# AstroEQ_SMD_V4_7_EQ5.net
KiCad netlist of a schematic drawn in EAGLE
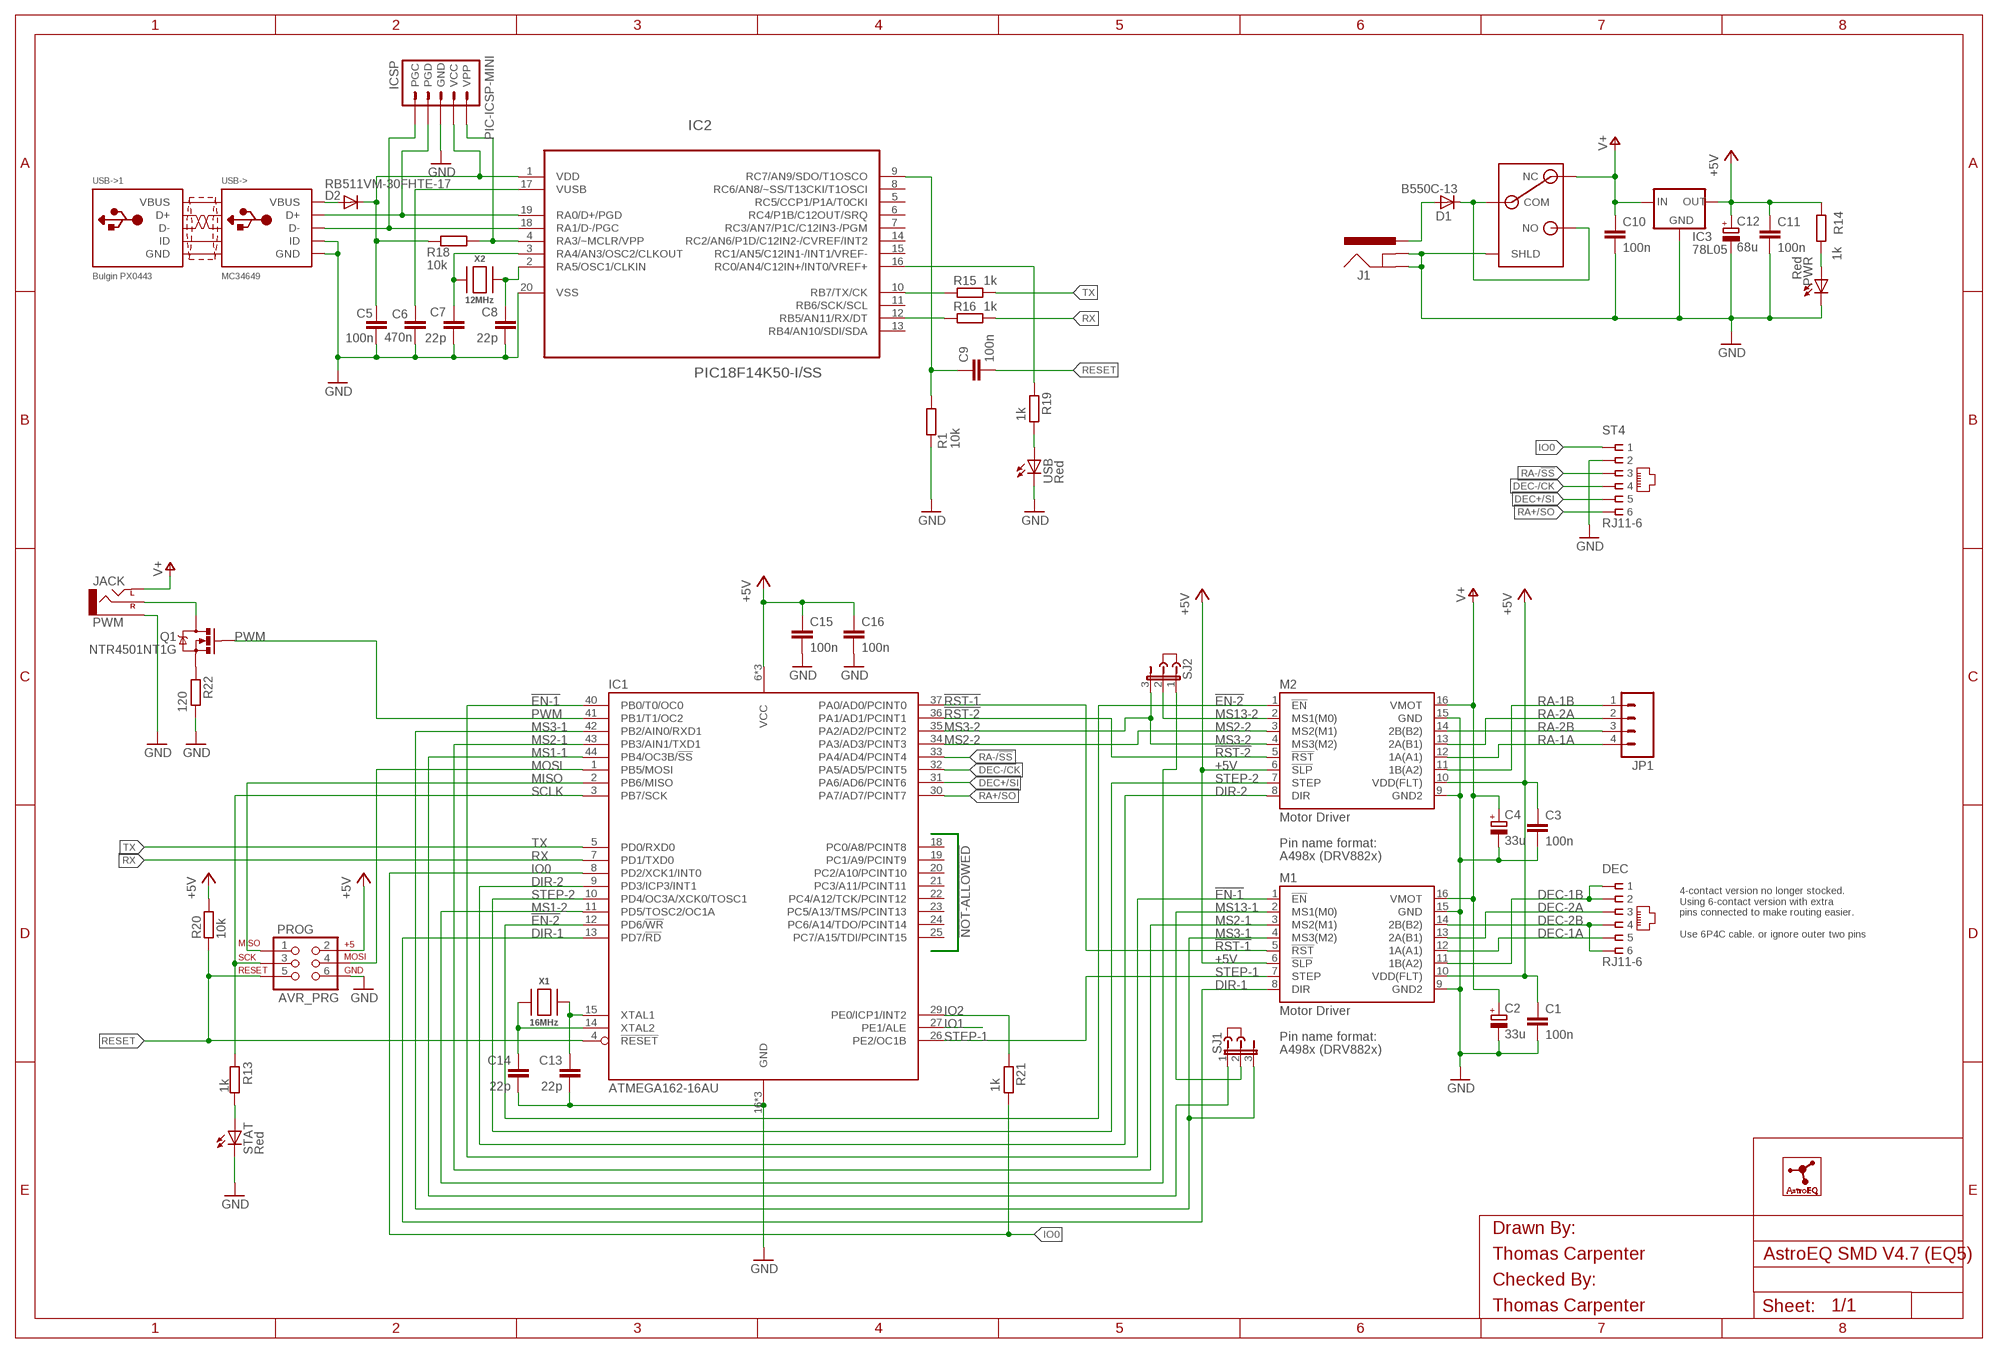
[diagram p0: schematic, sheet 1]

(export (version "E")
  (design (tool "Eeschema 10.0.6"))
  (components
    (comp (ref "C1")
      (value "100n")
      (footprint "eagle-import:C0603")
      (fields (field (name "MF") "MULTICOMP") (field (name "MPN") "MC0603F104Z250CT"))
      (libsource (lib "eagle-import") (part "C-EUC0603"))
    )
    (comp (ref "C2")
      (value "33u")
      (footprint "eagle-import:SMC_C")
      (fields (field (name "MF") "KEMET") (field (name "MPN") "T491C336K025AT"))
      (libsource (lib "eagle-import") (part "CPOL-EUSMCC"))
    )
    (comp (ref "C3")
      (value "100n")
      (footprint "eagle-import:C0603")
      (fields (field (name "MF") "MULTICOMP") (field (name "MPN") "MC0603F104Z250CT"))
      (libsource (lib "eagle-import") (part "C-EUC0603"))
    )
    (comp (ref "C4")
      (value "33u")
      (footprint "eagle-import:SMC_C")
      (fields (field (name "MF") "KEMET") (field (name "MPN") "T491C336K025AT"))
      (libsource (lib "eagle-import") (part "CPOL-EUSMCC"))
    )
    (comp (ref "C5")
      (value "100n")
      (footprint "eagle-import:C0603")
      (fields (field (name "MF") "MULTICOMP") (field (name "MPN") "MC0603F104Z250CT"))
      (libsource (lib "eagle-import") (part "C-EUC0603"))
    )
    (comp (ref "C6")
      (value "470n")
      (footprint "eagle-import:C0603")
      (fields (field (name "MF") "MULTICOMP") (field (name "MPN") "MC0603F474Z160CT"))
      (libsource (lib "eagle-import") (part "C-EUC0603"))
    )
    (comp (ref "C7")
      (value "22p")
      (footprint "eagle-import:C0603")
      (fields (field (name "MF") "MULTICOMP") (field (name "MPN") "MC0603N220J500CT"))
      (libsource (lib "eagle-import") (part "C-EUC0603"))
    )
    (comp (ref "C8")
      (value "22p")
      (footprint "eagle-import:C0603")
      (fields (field (name "MF") "MULTICOMP") (field (name "MPN") "MC0603N220J500CT"))
      (libsource (lib "eagle-import") (part "C-EUC0603"))
    )
    (comp (ref "C9")
      (value "100n")
      (footprint "eagle-import:C0603")
      (fields (field (name "MF") "MULTICOMP") (field (name "MPN") "MC0603F104Z250CT"))
      (libsource (lib "eagle-import") (part "C-EUC0603"))
    )
    (comp (ref "C10")
      (value "100n")
      (footprint "eagle-import:C0603")
      (fields (field (name "MF") "MULTICOMP") (field (name "MPN") "MC0603F104Z250CT"))
      (libsource (lib "eagle-import") (part "C-EUC0603"))
    )
    (comp (ref "C11")
      (value "100n")
      (footprint "eagle-import:C0603")
      (fields (field (name "MF") "MULTICOMP") (field (name "MPN") "MC0603F104Z250CT"))
      (libsource (lib "eagle-import") (part "C-EUC0603"))
    )
    (comp (ref "C12")
      (value "68u")
      (footprint "eagle-import:SMC_C")
      (fields (field (name "MF") "AVX") (field (name "MPN") "TPSC686K016R0125"))
      (libsource (lib "eagle-import") (part "CPOL-EUSMCC"))
    )
    (comp (ref "C13")
      (value "22p")
      (footprint "eagle-import:C0603")
      (fields (field (name "MF") "MULTICOMP") (field (name "MPN") "MC0603N220J500CT"))
      (libsource (lib "eagle-import") (part "C-EUC0603"))
    )
    (comp (ref "C14")
      (value "22p")
      (footprint "eagle-import:C0603")
      (fields (field (name "MF") "MULTICOMP") (field (name "MPN") "MC0603N220J500CT"))
      (libsource (lib "eagle-import") (part "C-EUC0603"))
    )
    (comp (ref "C15")
      (value "100n")
      (footprint "eagle-import:C0603")
      (fields (field (name "MF") "MULTICOMP") (field (name "MPN") "MC0603F104Z250CT"))
      (libsource (lib "eagle-import") (part "C-EUC0603"))
    )
    (comp (ref "C16")
      (value "100n")
      (footprint "eagle-import:C0603")
      (fields (field (name "MF") "MULTICOMP") (field (name "MPN") "MC0603F104Z250CT"))
      (libsource (lib "eagle-import") (part "C-EUC0603"))
    )
    (comp (ref "D1")
      (value "B550C-13")
      (footprint "eagle-import:SMC")
      (fields (field (name "MF") "DIODES INC.") (field (name "MPN") "B550C-13-F"))
      (libsource (lib "eagle-import") (part "DIODE-SMC"))
    )
    (comp (ref "D2")
      (value "RB511VM-30FHTE-17")
      (footprint "eagle-import:SOD-323")
      (fields (field (name "MF") "ROHM"))
      (libsource (lib "eagle-import") (part "DIODESOD"))
    )
    (comp (ref "DEC")
      (value "RJ11-6")
      (footprint "eagle-import:RJ11-NO_SHIELD")
      (fields
        (field (name "MF") "TYCO ELECTRONICS")
        (field (name "MPN") "RJ11-2L-B")
        (field (name "MF_1") "MOLEX")
        (field (name "MPN_1") "95503-2661")
        (field (name "OC_FARNELL") "1620210")
      )
      (libsource (lib "eagle-import") (part "RJ11-2L-B"))
    )
    (comp (ref "IC1")
      (value "ATMEGA162-16AU")
      (footprint "eagle-import:TQFP44")
      (fields (field (name "MF") "ATMEL"))
      (libsource (lib "eagle-import") (part "ATMEGA162-16AU"))
    )
    (comp (ref "IC2")
      (value "PIC18F14K50-I/SS")
      (footprint "eagle-import:SS20")
      (fields (field (name "MF") "MICROCHIP"))
      (libsource (lib "eagle-import") (part "PIC18F14K50/SS-I"))
    )
    (comp (ref "IC3")
      (value "78L05")
      (footprint "eagle-import:SOT23")
      (fields (field (name "MF") "TAIWAN SEMICONDUCTOR") (field (name "MPN") "TS78L05CX RFG"))
      (libsource (lib "eagle-import") (part "78LXXSOT-23"))
    )
    (comp (ref "ICSP")
      (value "PIC-ICSP-MINI")
      (footprint "eagle-import:PIC-ICSP-MINI")
      (libsource (lib "eagle-import") (part "PIC-ICSP-MINI"))
    )
    (comp (ref "J1")
      (value "POWER_JACKPANEL")
      (footprint "eagle-import:POWER_JACK_PANEL")
      (fields (field (name "MF") "SWITCHCRAFT") (field (name "MPN") "PCL712AS"))
      (libsource (lib "eagle-import") (part "POWER_JACKPANEL"))
    )
    (comp (ref "J2")
      (value "JUMPER")
      (footprint "eagle-import:JUMP")
      (fields (field (name "MF") "3M") (field (name "MPN") "969102-0000-DA"))
      (libsource (lib "eagle-import") (part "JUMPER"))
    )
    (comp (ref "J3")
      (value "JUMPER")
      (footprint "eagle-import:JUMP")
      (fields (field (name "MF") "3M") (field (name "MPN") "969102-0000-DA"))
      (libsource (lib "eagle-import") (part "JUMPER"))
    )
    (comp (ref "JP1")
      (value "M04POLAR")
      (footprint "eagle-import:MOLEX-1X4")
      (fields (field (name "MF") "MULTICOMP") (field (name "MPN") "MC34645"))
      (libsource (lib "eagle-import") (part "M04POLAR"))
    )
    (comp (ref "LOGO1")
      (value "ASTROEQ5MM")
      (footprint "eagle-import:ASTROEQ-SMALL")
      (libsource (lib "eagle-import") (part "ASTROEQ5MM"))
    )
    (comp (ref "M1")
      (value "Motor Driver")
      (footprint "eagle-import:DIP16-W")
      (fields (field (name "MF") "SAMTEC") (field (name "MPN") "CES-116-01-T-S"))
      (libsource (lib "eagle-import") (part "A4983CARRIER"))
    )
    (comp (ref "M2")
      (value "Motor Driver")
      (footprint "eagle-import:DIP16-W")
      (fields (field (name "MF") "SAMTEC") (field (name "MPN") "CES-116-01-T-S"))
      (libsource (lib "eagle-import") (part "A4983CARRIER"))
    )
    (comp (ref "PROG")
      (value "AVR_PRG")
      (footprint "eagle-import:2X3")
      (fields (field (name "MF") "AMP - TE CONNECTIVITY") (field (name "MPN") "826632-3"))
      (libsource (lib "eagle-import") (part "AVR_SPI_PRG_6PTH"))
    )
    (comp (ref "PWM")
      (value "JACK")
      (footprint "eagle-import:AUDIO-JACK-3.5MM-VERT")
      (fields (field (name "MANUFACTURER") "LUMBERG") (field (name "MPN") "1502 01"))
      (libsource (lib "eagle-import") (part "AUDIO-JACKVERT"))
    )
    (comp (ref "PWR")
      (value "Red")
      (footprint "eagle-import:LED3MM")
      (fields (field (name "MF") "KINGBRIGHT") (field (name "MPN") "L-424HDT"))
      (libsource (lib "eagle-import") (part "LED3MM"))
    )
    (comp (ref "PWR-SW")
      (value "SWITCH")
      (footprint "eagle-import:SPST")
      (fields (field (name "MF") "TE CONNECTIVITY") (field (name "MPN") "AE101J1V3B004"))
      (libsource (lib "eagle-import") (part "SWITCH"))
    )
    (comp (ref "Q1")
      (value "NTR4501NT1G")
      (footprint "eagle-import:SOT23-3")
      (fields (field (name "MF") "ON SEMICONDUCTOR"))
      (libsource (lib "eagle-import") (part "MOSFET-NCHANNELSMD"))
    )
    (comp (ref "R1")
      (value "10k")
      (footprint "eagle-import:R0603")
      (fields (field (name "MF") "MULTICOMP") (field (name "MPN") "MCWR06X1002FTL"))
      (libsource (lib "eagle-import") (part "R-EU_R0603"))
    )
    (comp (ref "R13")
      (value "1k")
      (footprint "eagle-import:R0603")
      (fields (field (name "MF") "MULTICOMP") (field (name "MPN") "MCWR06X1001FTL"))
      (libsource (lib "eagle-import") (part "R-EU_R0603"))
    )
    (comp (ref "R14")
      (value "1k")
      (footprint "eagle-import:R0603")
      (fields (field (name "MF") "MULTICOMP") (field (name "MPN") "MCWR06X1001FTL"))
      (libsource (lib "eagle-import") (part "R-EU_R0603"))
    )
    (comp (ref "R15")
      (value "1k")
      (footprint "eagle-import:R0603")
      (fields (field (name "MF") "MULTICOMP") (field (name "MPN") "MCWR06X1001FTL"))
      (libsource (lib "eagle-import") (part "R-EU_R0603"))
    )
    (comp (ref "R16")
      (value "1k")
      (footprint "eagle-import:R0603")
      (fields (field (name "MF") "MULTICOMP") (field (name "MPN") "MCWR06X1001FTL"))
      (libsource (lib "eagle-import") (part "R-EU_R0603"))
    )
    (comp (ref "R18")
      (value "10k")
      (footprint "eagle-import:R0603")
      (fields (field (name "MF") "MULTICOMP") (field (name "MPN") "MCWR06X1002FTL"))
      (libsource (lib "eagle-import") (part "R-EU_R0603"))
    )
    (comp (ref "R19")
      (value "1k")
      (footprint "eagle-import:R0603")
      (fields (field (name "MF") "MULTICOMP") (field (name "MPN") "MCWR06X1001FTL"))
      (libsource (lib "eagle-import") (part "R-EU_R0603"))
    )
    (comp (ref "R20")
      (value "10k")
      (footprint "eagle-import:R0603")
      (fields (field (name "MF") "MULTICOMP") (field (name "MPN") "MCWR06X1002FTL"))
      (libsource (lib "eagle-import") (part "R-EU_R0603"))
    )
    (comp (ref "R21")
      (value "1k")
      (footprint "eagle-import:R0603")
      (fields (field (name "MF") "MULTICOMP") (field (name "MPN") "MCWR06X1001FTL"))
      (libsource (lib "eagle-import") (part "R-EU_R0603"))
    )
    (comp (ref "R22")
      (value "120")
      (footprint "eagle-import:R0805")
      (fields (field (name "MF") "MULTICOMP") (field (name "MPN") "MCWR08X1200FTL"))
      (libsource (lib "eagle-import") (part "R-EU_R0805"))
    )
    (comp (ref "SJ1")
      (value "JP2E")
      (footprint "eagle-import:JP2")
      (fields (field (name "MF") "MULTICOMP") (field (name "MPN") "2211S-03G"))
      (libsource (lib "eagle-import") (part "JP2E"))
    )
    (comp (ref "SJ2")
      (value "JP2E")
      (footprint "eagle-import:JP2")
      (fields (field (name "MF") "MULTICOMP") (field (name "MPN") "2211S-03G"))
      (libsource (lib "eagle-import") (part "JP2E"))
    )
    (comp (ref "ST4")
      (value "RJ11-6")
      (footprint "eagle-import:RJ11-NO_SHIELD")
      (fields
        (field (name "MF") "TYCO ELECTRONICS")
        (field (name "MPN") "RJ11-2L-B")
        (field (name "MF_1") "MOLEX")
        (field (name "MPN_1") "95503-2661")
        (field (name "OC_FARNELL") "1620210")
      )
      (libsource (lib "eagle-import") (part "RJ11-2L-B"))
    )
    (comp (ref "STAT")
      (value "Red")
      (footprint "eagle-import:LED3MM")
      (fields (field (name "MF") "KINGBRIGHT") (field (name "MPN") "L-424HDT"))
      (libsource (lib "eagle-import") (part "LED3MM"))
    )
    (comp (ref "USB")
      (value "Red")
      (footprint "eagle-import:LED3MM")
      (fields (field (name "MF") "KINGBRIGHT") (field (name "MPN") "L-424HDT"))
      (libsource (lib "eagle-import") (part "LED3MM"))
    )
    (comp (ref "USB->")
      (value "MC34649")
      (footprint "eagle-import:22-23-2051")
      (fields (field (name "MF") "MULTICOMP"))
      (libsource (lib "eagle-import") (part "USBBULGINWIRE"))
    )
    (comp (ref "X1")
      (value "16MHz")
      (footprint "eagle-import:NX5032")
      (fields (field (name "MF") "TXC") (field (name "MPN") "7A-16.000MAAJ-T"))
      (libsource (lib "eagle-import") (part "XTALNX5032"))
    )
    (comp (ref "X2")
      (value "12MHz")
      (footprint "eagle-import:NX5032")
      (fields (field (name "MF") "TXC") (field (name "MPN") "7A-12.000MAAJ-T"))
      (libsource (lib "eagle-import") (part "XTALNX5032"))
    )
  )
  (nets
    (net (code "1") (name "+5V") (class "Default")
      (node (ref "C1") (pin "1") (pinfunction "1_1") (pintype "passive"))
      (node (ref "C11") (pin "1") (pinfunction "1_1") (pintype "passive"))
      (node (ref "C12") (pin "+") (pinfunction "+_+") (pintype "passive"))
      (node (ref "C15") (pin "1") (pinfunction "1_1") (pintype "passive"))
      (node (ref "C16") (pin "1") (pinfunction "1_1") (pintype "passive"))
      (node (ref "C3") (pin "1") (pinfunction "1_1") (pintype "passive"))
      (node (ref "IC1") (pin "17") (pinfunction "VCC_17") (pintype "power_in"))
      (node (ref "IC1") (pin "38") (pinfunction "VCC_38") (pintype "power_in"))
      (node (ref "IC1") (pin "6") (pinfunction "VCC_6") (pintype "power_in"))
      (node (ref "IC3") (pin "1") (pinfunction "OUT_1") (pintype "passive"))
      (node (ref "M1") (pin "10") (pinfunction "VDD(FLT)_10") (pintype "power_in"))
      (node (ref "M1") (pin "6") (pinfunction "~{SLP}_6") (pintype "input"))
      (node (ref "M2") (pin "10") (pinfunction "VDD(FLT)_10") (pintype "power_in"))
      (node (ref "M2") (pin "6") (pinfunction "~{SLP}_6") (pintype "input"))
      (node (ref "PROG") (pin "2") (pinfunction "2_2") (pintype "passive"))
      (node (ref "R14") (pin "1") (pinfunction "1_1") (pintype "passive"))
      (node (ref "R20") (pin "2") (pinfunction "2_2") (pintype "passive"))
    )
    (net (code "2") (name "/DEC-1A") (class "Default")
      (node (ref "DEC") (pin "5") (pinfunction "5_5") (pintype "passive"))
      (node (ref "M1") (pin "12") (pinfunction "1A(A1)_12") (pintype "output"))
    )
    (net (code "3") (name "/DEC-1B") (class "Default")
      (node (ref "DEC") (pin "1") (pinfunction "1_1") (pintype "passive"))
      (node (ref "DEC") (pin "2") (pinfunction "2_2") (pintype "passive"))
      (node (ref "M1") (pin "11") (pinfunction "1B(A2)_11") (pintype "output"))
    )
    (net (code "4") (name "/DEC-2A") (class "Default")
      (node (ref "DEC") (pin "3") (pinfunction "3_3") (pintype "passive"))
      (node (ref "M1") (pin "13") (pinfunction "2A(B1)_13") (pintype "output"))
    )
    (net (code "5") (name "/DEC-2B") (class "Default")
      (node (ref "DEC") (pin "4") (pinfunction "4_4") (pintype "passive"))
      (node (ref "DEC") (pin "6") (pinfunction "6_6") (pintype "passive"))
      (node (ref "M1") (pin "14") (pinfunction "2B(B2)_14") (pintype "output"))
    )
    (net (code "6") (name "/DIR-1") (class "Default")
      (node (ref "IC1") (pin "13") (pinfunction "PD7/~{RD}_13") (pintype "bidirectional"))
      (node (ref "M1") (pin "8") (pinfunction "DIR_8") (pintype "input"))
    )
    (net (code "7") (name "/DIR-2") (class "Default")
      (node (ref "IC1") (pin "9") (pinfunction "PD3/ICP3/INT1_9") (pintype "bidirectional"))
      (node (ref "M2") (pin "8") (pinfunction "DIR_8") (pintype "input"))
    )
    (net (code "8") (name "/IO1") (class "Default")
      (node (ref "IC1") (pin "27") (pinfunction "PE1/ALE_27") (pintype "bidirectional"))
    )
    (net (code "9") (name "/IO2") (class "Default")
      (node (ref "IC1") (pin "29") (pinfunction "PE0/ICP1/INT2_29") (pintype "bidirectional"))
      (node (ref "R21") (pin "2") (pinfunction "2_2") (pintype "passive"))
    )
    (net (code "10") (name "/MISO") (class "Default")
      (node (ref "IC1") (pin "2") (pinfunction "PB6/MISO_2") (pintype "bidirectional"))
      (node (ref "PROG") (pin "1") (pinfunction "1_1") (pintype "passive"))
    )
    (net (code "11") (name "/MOSI") (class "Default")
      (node (ref "IC1") (pin "1") (pinfunction "PB5/MOSI_1") (pintype "bidirectional"))
      (node (ref "PROG") (pin "4") (pinfunction "4_4") (pintype "passive"))
    )
    (net (code "12") (name "/MS1-1") (class "Default")
      (node (ref "IC1") (pin "44") (pinfunction "PB4/OC3B/~{SS}_44") (pintype "bidirectional"))
      (node (ref "SJ1") (pin "1") (pinfunction "1_1") (pintype "passive"))
    )
    (net (code "13") (name "/MS1-2") (class "Default")
      (node (ref "IC1") (pin "11") (pinfunction "PD5/TOSC2/OC1A_11") (pintype "bidirectional"))
      (node (ref "SJ2") (pin "1") (pinfunction "1_1") (pintype "passive"))
    )
    (net (code "14") (name "/MS2-1") (class "Default")
      (node (ref "IC1") (pin "43") (pinfunction "PB3/AIN1/TXD1_43") (pintype "bidirectional"))
      (node (ref "M1") (pin "3") (pinfunction "MS2(M1)_3") (pintype "input"))
    )
    (net (code "15") (name "/MS2-2") (class "Default")
      (node (ref "IC1") (pin "34") (pinfunction "PA3/AD3/PCINT3_34") (pintype "bidirectional"))
      (node (ref "M2") (pin "3") (pinfunction "MS2(M1)_3") (pintype "input"))
    )
    (net (code "16") (name "/MS3-1") (class "Default")
      (node (ref "IC1") (pin "42") (pinfunction "PB2/AIN0/RXD1_42") (pintype "bidirectional"))
      (node (ref "M1") (pin "4") (pinfunction "MS3(M2)_4") (pintype "input"))
      (node (ref "SJ1") (pin "3") (pinfunction "3_3") (pintype "passive"))
    )
    (net (code "17") (name "/MS3-2") (class "Default")
      (node (ref "IC1") (pin "35") (pinfunction "PA2/AD2/PCINT2_35") (pintype "bidirectional"))
      (node (ref "M2") (pin "4") (pinfunction "MS3(M2)_4") (pintype "input"))
      (node (ref "SJ2") (pin "3") (pinfunction "3_3") (pintype "passive"))
    )
    (net (code "18") (name "/MS13-1") (class "Default")
      (node (ref "M1") (pin "2") (pinfunction "MS1(M0)_2") (pintype "input"))
      (node (ref "SJ1") (pin "2") (pinfunction "2_2") (pintype "passive"))
    )
    (net (code "19") (name "/MS13-2") (class "Default")
      (node (ref "M2") (pin "2") (pinfunction "MS1(M0)_2") (pintype "input"))
      (node (ref "SJ2") (pin "2") (pinfunction "2_2") (pintype "passive"))
    )
    (net (code "20") (name "/PWM") (class "Default")
      (node (ref "IC1") (pin "41") (pinfunction "PB1/T1/OC2_41") (pintype "bidirectional"))
      (node (ref "Q1") (pin "1") (pinfunction "G_1") (pintype "passive"))
    )
    (net (code "21") (name "/RA-1A") (class "Default")
      (node (ref "JP1") (pin "4") (pinfunction "4_4") (pintype "passive"))
      (node (ref "M2") (pin "12") (pinfunction "1A(A1)_12") (pintype "output"))
    )
    (net (code "22") (name "/RA-1B") (class "Default")
      (node (ref "JP1") (pin "1") (pinfunction "1_1") (pintype "passive"))
      (node (ref "M2") (pin "11") (pinfunction "1B(A2)_11") (pintype "output"))
    )
    (net (code "23") (name "/RA-2A") (class "Default")
      (node (ref "JP1") (pin "2") (pinfunction "2_2") (pintype "passive"))
      (node (ref "M2") (pin "13") (pinfunction "2A(B1)_13") (pintype "output"))
    )
    (net (code "24") (name "/RA-2B") (class "Default")
      (node (ref "JP1") (pin "3") (pinfunction "3_3") (pintype "passive"))
      (node (ref "M2") (pin "14") (pinfunction "2B(B2)_14") (pintype "output"))
    )
    (net (code "25") (name "/RA-{slash}~{SS}") (class "Default")
      (node (ref "IC1") (pin "33") (pinfunction "PA4/AD4/PCINT4_33") (pintype "bidirectional"))
      (node (ref "ST4") (pin "3") (pinfunction "3_3") (pintype "passive"))
    )
    (net (code "26") (name "/SCLK") (class "Default")
      (node (ref "IC1") (pin "3") (pinfunction "PB7/SCK_3") (pintype "bidirectional"))
      (node (ref "PROG") (pin "3") (pinfunction "3_3") (pintype "passive"))
      (node (ref "R13") (pin "1") (pinfunction "1_1") (pintype "passive"))
    )
    (net (code "27") (name "/STEP-1") (class "Default")
      (node (ref "IC1") (pin "26") (pinfunction "PE2/OC1B_26") (pintype "bidirectional"))
      (node (ref "M1") (pin "7") (pinfunction "STEP_7") (pintype "input"))
    )
    (net (code "28") (name "/STEP-2") (class "Default")
      (node (ref "IC1") (pin "10") (pinfunction "PD4/OC3A/XCK0/TOSC1_10") (pintype "bidirectional"))
      (node (ref "M2") (pin "7") (pinfunction "STEP_7") (pintype "input"))
    )
    (net (code "29") (name "/~{EN-1}") (class "Default")
      (node (ref "IC1") (pin "40") (pinfunction "PB0/T0/OC0_40") (pintype "bidirectional"))
      (node (ref "M1") (pin "1") (pinfunction "~{EN}_1") (pintype "input"))
    )
    (net (code "30") (name "/~{EN-2}") (class "Default")
      (node (ref "IC1") (pin "12") (pinfunction "PD6/~{WR}_12") (pintype "bidirectional"))
      (node (ref "M2") (pin "1") (pinfunction "~{EN}_1") (pintype "input"))
    )
    (net (code "32") (name "/~{RST-1}") (class "Default")
      (node (ref "IC1") (pin "37") (pinfunction "PA0/AD0/PCINT0_37") (pintype "bidirectional"))
      (node (ref "M1") (pin "5") (pinfunction "~{RST}_5") (pintype "input"))
    )
    (net (code "33") (name "/~{RST-2}") (class "Default")
      (node (ref "IC1") (pin "36") (pinfunction "PA1/AD1/PCINT1_36") (pintype "bidirectional"))
      (node (ref "M2") (pin "5") (pinfunction "~{RST}_5") (pintype "input"))
    )
    (net (code "34") (name "DEC+{slash}SI") (class "Default")
      (node (ref "IC1") (pin "31") (pinfunction "PA6/AD6/PCINT6_31") (pintype "bidirectional"))
      (node (ref "ST4") (pin "5") (pinfunction "5_5") (pintype "passive"))
    )
    (net (code "35") (name "DEC-{slash}CK") (class "Default")
      (node (ref "IC1") (pin "32") (pinfunction "PA5/AD5/PCINT5_32") (pintype "bidirectional"))
      (node (ref "ST4") (pin "4") (pinfunction "4_4") (pintype "passive"))
    )
    (net (code "36") (name "GND") (class "Default")
      (node (ref "C1") (pin "2") (pinfunction "2_2") (pintype "passive"))
      (node (ref "C10") (pin "2") (pinfunction "2_2") (pintype "passive"))
      (node (ref "C11") (pin "2") (pinfunction "2_2") (pintype "passive"))
      (node (ref "C12") (pin "-") (pinfunction "-_-") (pintype "passive"))
      (node (ref "C13") (pin "2") (pinfunction "2_2") (pintype "passive"))
      (node (ref "C14") (pin "2") (pinfunction "2_2") (pintype "passive"))
      (node (ref "C15") (pin "2") (pinfunction "2_2") (pintype "passive"))
      (node (ref "C16") (pin "2") (pinfunction "2_2") (pintype "passive"))
      (node (ref "C2") (pin "-") (pinfunction "-_-") (pintype "passive"))
      (node (ref "C3") (pin "2") (pinfunction "2_2") (pintype "passive"))
      (node (ref "C4") (pin "-") (pinfunction "-_-") (pintype "passive"))
      (node (ref "C5") (pin "2") (pinfunction "2_2") (pintype "passive"))
      (node (ref "C6") (pin "1") (pinfunction "1_1") (pintype "passive"))
      (node (ref "C7") (pin "2") (pinfunction "2_2") (pintype "passive"))
      (node (ref "C8") (pin "2") (pinfunction "2_2") (pintype "passive"))
      (node (ref "IC1") (pin "16") (pinfunction "GND_16") (pintype "power_in"))
      (node (ref "IC1") (pin "28") (pinfunction "GND_28") (pintype "power_in"))
      (node (ref "IC1") (pin "39") (pinfunction "GND_39") (pintype "power_in"))
      (node (ref "IC2") (pin "20") (pinfunction "VSS_20") (pintype "power_in"))
      (node (ref "IC3") (pin "3") (pinfunction "GND_3") (pintype "input"))
      (node (ref "ICSP") (pin "3") (pinfunction "GND_3") (pintype "passive"))
      (node (ref "J1") (pin "SHUNT") (pinfunction "GNDBREAK_SHUNT") (pintype "bidirectional"))
      (node (ref "J1") (pin "SLEEVE") (pinfunction "GND_SLEEVE") (pintype "bidirectional"))
      (node (ref "M1") (pin "15") (pinfunction "GND_15") (pintype "power_in"))
      (node (ref "M1") (pin "9") (pinfunction "GND2_9") (pintype "power_in"))
      (node (ref "M2") (pin "15") (pinfunction "GND_15") (pintype "power_in"))
      (node (ref "M2") (pin "9") (pinfunction "GND2_9") (pintype "power_in"))
      (node (ref "PROG") (pin "6") (pinfunction "6_6") (pintype "passive"))
      (node (ref "PWM") (pin "1") (pinfunction "SLEEVE_1") (pintype "bidirectional"))
      (node (ref "PWR") (pin "K") (pinfunction "C_K") (pintype "passive"))
      (node (ref "PWR-SW") (pin "S1") (pinfunction "SHLD_S1") (pintype "bidirectional"))
      (node (ref "PWR-SW") (pin "S2") (pinfunction "SHLD_S2") (pintype "bidirectional"))
      (node (ref "PWR-SW") (pin "S3") (pinfunction "SHLD_S3") (pintype "bidirectional"))
      (node (ref "PWR-SW") (pin "S4") (pinfunction "SHLD_S4") (pintype "bidirectional"))
      (node (ref "R1") (pin "2") (pinfunction "2_2") (pintype "passive"))
      (node (ref "R22") (pin "1") (pinfunction "1_1") (pintype "passive"))
      (node (ref "ST4") (pin "2") (pinfunction "2_2") (pintype "passive"))
      (node (ref "STAT") (pin "K") (pinfunction "C_K") (pintype "passive"))
      (node (ref "USB") (pin "K") (pinfunction "C_K") (pintype "passive"))
      (node (ref "USB->") (pin "4") (pinfunction "GND_4") (pintype "power_in"))
      (node (ref "USB->") (pin "5") (pinfunction "ID_5") (pintype "bidirectional"))
    )
    (net (code "37") (name "IO0") (class "Default")
      (node (ref "IC1") (pin "8") (pinfunction "PD2/XCK1/INT0_8") (pintype "bidirectional"))
      (node (ref "R21") (pin "1") (pinfunction "1_1") (pintype "passive"))
      (node (ref "ST4") (pin "1") (pinfunction "1_1") (pintype "passive"))
    )
    (net (code "38") (name "Net-(D1-PadC)") (class "Default")
      (node (ref "D1") (pin "C") (pinfunction "C_C") (pintype "passive"))
      (node (ref "PWR-SW") (pin "COM") (pinfunction "COM_COM") (pintype "passive"))
      (node (ref "PWR-SW") (pin "NO") (pinfunction "NO_NO") (pintype "passive"))
    )
    (net (code "39") (name "Net-(D2-A)") (class "Default")
      (node (ref "D2") (pin "2") (pinfunction "A_2") (pintype "passive"))
      (node (ref "USB->") (pin "1") (pinfunction "VBUS_1") (pintype "power_in"))
    )
    (net (code "40") (name "Net-(D2-C)") (class "Default")
      (node (ref "C5") (pin "1") (pinfunction "1_1") (pintype "passive"))
      (node (ref "D2") (pin "1") (pinfunction "C_1") (pintype "passive"))
      (node (ref "IC2") (pin "1") (pinfunction "VDD_1") (pintype "power_in"))
      (node (ref "ICSP") (pin "2") (pinfunction "VCC_2") (pintype "passive"))
      (node (ref "R18") (pin "2") (pinfunction "2_2") (pintype "passive"))
    )
    (net (code "41") (name "Net-(IC1-XTAL1)") (class "Default")
      (node (ref "C13") (pin "1") (pinfunction "1_1") (pintype "passive"))
      (node (ref "IC1") (pin "15") (pinfunction "XTAL1_15") (pintype "input"))
      (node (ref "X1") (pin "P$1") (pinfunction "P$1_P$1") (pintype "bidirectional"))
    )
    (net (code "42") (name "Net-(IC1-XTAL2)") (class "Default")
      (node (ref "C14") (pin "1") (pinfunction "1_1") (pintype "passive"))
      (node (ref "IC1") (pin "14") (pinfunction "XTAL2_14") (pintype "input"))
      (node (ref "X1") (pin "P$2") (pinfunction "P$2_P$2") (pintype "bidirectional"))
    )
    (net (code "43") (name "Net-(IC2-RA0{slash}D+{slash}PGD)") (class "Default")
      (node (ref "IC2") (pin "19") (pinfunction "RA0/D+/PGD_19") (pintype "bidirectional"))
      (node (ref "ICSP") (pin "4") (pinfunction "PGD_4") (pintype "passive"))
      (node (ref "USB->") (pin "3") (pinfunction "D+_3") (pintype "bidirectional"))
    )
    (net (code "44") (name "Net-(IC2-RA1{slash}D-{slash}PGC)") (class "Default")
      (node (ref "IC2") (pin "18") (pinfunction "RA1/D-/PGC_18") (pintype "bidirectional"))
      (node (ref "ICSP") (pin "5") (pinfunction "PGC_5") (pintype "passive"))
      (node (ref "USB->") (pin "2") (pinfunction "D-_2") (pintype "bidirectional"))
    )
    (net (code "45") (name "Net-(IC2-RA3{slash}~{MCLR{slash}VPP})") (class "Default")
      (node (ref "IC2") (pin "4") (pinfunction "RA3/~{MCLR/VPP}_4") (pintype "input"))
      (node (ref "ICSP") (pin "1") (pinfunction "VPP_1") (pintype "passive"))
      (node (ref "R18") (pin "1") (pinfunction "1_1") (pintype "passive"))
    )
    (net (code "46") (name "Net-(IC2-RA4{slash}AN3{slash}OSC2{slash}CLKOUT)") (class "Default")
      (node (ref "C7") (pin "1") (pinfunction "1_1") (pintype "passive"))
      (node (ref "IC2") (pin "3") (pinfunction "RA4/AN3/OSC2/CLKOUT_3") (pintype "bidirectional"))
      (node (ref "X2") (pin "P$1") (pinfunction "P$1_P$1") (pintype "bidirectional"))
    )
    (net (code "47") (name "Net-(IC2-RA5{slash}OSC1{slash}CLKIN)") (class "Default")
      (node (ref "C8") (pin "1") (pinfunction "1_1") (pintype "passive"))
      (node (ref "IC2") (pin "2") (pinfunction "RA5/OSC1/CLKIN_2") (pintype "bidirectional"))
      (node (ref "X2") (pin "P$2") (pinfunction "P$2_P$2") (pintype "bidirectional"))
    )
    (net (code "48") (name "Net-(IC2-RB5{slash}AN11{slash}RX{slash}DT)") (class "Default")
      (node (ref "IC2") (pin "12") (pinfunction "RB5/AN11/RX/DT_12") (pintype "bidirectional"))
      (node (ref "R16") (pin "2") (pinfunction "2_2") (pintype "passive"))
    )
    (net (code "49") (name "Net-(IC2-RB7{slash}TX{slash}CK)") (class "Default")
      (node (ref "IC2") (pin "10") (pinfunction "RB7/TX/CK_10") (pintype "bidirectional"))
      (node (ref "R15") (pin "2") (pinfunction "2_2") (pintype "passive"))
    )
    (net (code "50") (name "Net-(IC2-RC0{slash}AN4{slash}C12IN+{slash}INT0{slash}VREF+)") (class "Default")
      (node (ref "IC2") (pin "16") (pinfunction "RC0/AN4/C12IN+/INT0/VREF+_16") (pintype "bidirectional"))
      (node (ref "R19") (pin "2") (pinfunction "2_2") (pintype "passive"))
    )
    (net (code "51") (name "Net-(IC2-RC7{slash}AN9{slash}SDO{slash}T1OSCO)") (class "Default")
      (node (ref "C9") (pin "1") (pinfunction "1_1") (pintype "passive"))
      (node (ref "IC2") (pin "9") (pinfunction "RC7/AN9/SDO/T1OSCO_9") (pintype "bidirectional"))
      (node (ref "R1") (pin "1") (pinfunction "1_1") (pintype "passive"))
    )
    (net (code "52") (name "Net-(IC2-VUSB)") (class "Default")
      (node (ref "C6") (pin "2") (pinfunction "2_2") (pintype "passive"))
      (node (ref "IC2") (pin "17") (pinfunction "VUSB_17") (pintype "power_in"))
    )
    (net (code "53") (name "Net-(J1-PWR)") (class "Default")
      (node (ref "D1") (pin "A") (pinfunction "A_A") (pintype "passive"))
      (node (ref "J1") (pin "CENTRE") (pinfunction "PWR_CENTRE") (pintype "bidirectional"))
    )
    (net (code "54") (name "Net-(PWM-RIGHT)") (class "Default")
      (node (ref "PWM") (pin "3") (pinfunction "RIGHT_3") (pintype "bidirectional"))
      (node (ref "Q1") (pin "3") (pinfunction "D_3") (pintype "passive"))
    )
    (net (code "55") (name "Net-(PWR-PadA)") (class "Default")
      (node (ref "PWR") (pin "A") (pinfunction "A_A") (pintype "passive"))
      (node (ref "R14") (pin "2") (pinfunction "2_2") (pintype "passive"))
    )
    (net (code "56") (name "Net-(Q1-S)") (class "Default")
      (node (ref "Q1") (pin "2") (pinfunction "S_2") (pintype "passive"))
      (node (ref "R22") (pin "2") (pinfunction "2_2") (pintype "passive"))
    )
    (net (code "57") (name "Net-(R13-Pad2)") (class "Default")
      (node (ref "R13") (pin "2") (pinfunction "2_2") (pintype "passive"))
      (node (ref "STAT") (pin "A") (pinfunction "A_A") (pintype "passive"))
    )
    (net (code "58") (name "Net-(R19-Pad1)") (class "Default")
      (node (ref "R19") (pin "1") (pinfunction "1_1") (pintype "passive"))
      (node (ref "USB") (pin "A") (pinfunction "A_A") (pintype "passive"))
    )
    (net (code "59") (name "RA+{slash}SO") (class "Default")
      (node (ref "IC1") (pin "30") (pinfunction "PA7/AD7/PCINT7_30") (pintype "bidirectional"))
      (node (ref "ST4") (pin "6") (pinfunction "6_6") (pintype "passive"))
    )
    (net (code "60") (name "RESET") (class "Default")
      (node (ref "C9") (pin "2") (pinfunction "2_2") (pintype "passive"))
      (node (ref "IC1") (pin "4") (pinfunction "~{RESET}_4") (pintype "input"))
      (node (ref "PROG") (pin "5") (pinfunction "5_5") (pintype "passive"))
      (node (ref "R20") (pin "1") (pinfunction "1_1") (pintype "passive"))
    )
    (net (code "61") (name "RX") (class "Default")
      (node (ref "IC1") (pin "7") (pinfunction "PD1/TXD0_7") (pintype "bidirectional"))
      (node (ref "R16") (pin "1") (pinfunction "1_1") (pintype "passive"))
    )
    (net (code "62") (name "TX") (class "Default")
      (node (ref "IC1") (pin "5") (pinfunction "PD0/RXD0_5") (pintype "bidirectional"))
      (node (ref "R15") (pin "1") (pinfunction "1_1") (pintype "passive"))
    )
    (net (code "63") (name "V+") (class "Default")
      (node (ref "C10") (pin "1") (pinfunction "1_1") (pintype "passive"))
      (node (ref "C2") (pin "+") (pinfunction "+_+") (pintype "passive"))
      (node (ref "C4") (pin "+") (pinfunction "+_+") (pintype "passive"))
      (node (ref "IC3") (pin "2") (pinfunction "IN_2") (pintype "input"))
      (node (ref "M1") (pin "16") (pinfunction "VMOT_16") (pintype "power_in"))
      (node (ref "M2") (pin "16") (pinfunction "VMOT_16") (pintype "power_in"))
      (node (ref "PWM") (pin "2") (pinfunction "LEFT_2") (pintype "bidirectional"))
      (node (ref "PWR-SW") (pin "NC") (pinfunction "NC_NC") (pintype "passive"))
    )
    (net (code "64") (name "unconnected-(IC1-PC0{slash}A8{slash}PCINT8-Pad18)") (class "Default")
      (node (ref "IC1") (pin "18") (pinfunction "PC0/A8/PCINT8_18") (pintype "bidirectional"))
    )
    (net (code "65") (name "unconnected-(IC1-PC1{slash}A9{slash}PCINT9-Pad19)") (class "Default")
      (node (ref "IC1") (pin "19") (pinfunction "PC1/A9/PCINT9_19") (pintype "bidirectional"))
    )
    (net (code "66") (name "unconnected-(IC1-PC2{slash}A10{slash}PCINT10-Pad20)") (class "Default")
      (node (ref "IC1") (pin "20") (pinfunction "PC2/A10/PCINT10_20") (pintype "bidirectional"))
    )
    (net (code "67") (name "unconnected-(IC1-PC3{slash}A11{slash}PCINT11-Pad21)") (class "Default")
      (node (ref "IC1") (pin "21") (pinfunction "PC3/A11/PCINT11_21") (pintype "bidirectional"))
    )
    (net (code "68") (name "unconnected-(IC1-PC4{slash}A12{slash}TCK{slash}PCINT12-Pad22)") (class "Default")
      (node (ref "IC1") (pin "22") (pinfunction "PC4/A12/TCK/PCINT12_22") (pintype "bidirectional"))
    )
    (net (code "69") (name "unconnected-(IC1-PC5{slash}A13{slash}TMS{slash}PCINT13-Pad23)") (class "Default")
      (node (ref "IC1") (pin "23") (pinfunction "PC5/A13/TMS/PCINT13_23") (pintype "bidirectional"))
    )
    (net (code "70") (name "unconnected-(IC1-PC6{slash}A14{slash}TDO{slash}PCINT14-Pad24)") (class "Default")
      (node (ref "IC1") (pin "24") (pinfunction "PC6/A14/TDO/PCINT14_24") (pintype "bidirectional"))
    )
    (net (code "71") (name "unconnected-(IC1-PC7{slash}A15{slash}TDI{slash}PCINT15-Pad25)") (class "Default")
      (node (ref "IC1") (pin "25") (pinfunction "PC7/A15/TDI/PCINT15_25") (pintype "bidirectional"))
    )
    (net (code "72") (name "unconnected-(IC2-RB4{slash}AN10{slash}SDI{slash}SDA-Pad13)") (class "Default")
      (node (ref "IC2") (pin "13") (pinfunction "RB4/AN10/SDI/SDA_13") (pintype "bidirectional"))
    )
    (net (code "73") (name "unconnected-(IC2-RB6{slash}SCK{slash}SCL-Pad11)") (class "Default")
      (node (ref "IC2") (pin "11") (pinfunction "RB6/SCK/SCL_11") (pintype "bidirectional"))
    )
    (net (code "74") (name "unconnected-(IC2-RC1{slash}AN5{slash}C12IN1-{slash}INT1{slash}VREF--Pad15)") (class "Default")
      (node (ref "IC2") (pin "15") (pinfunction "RC1/AN5/C12IN1-/INT1/VREF-_15") (pintype "bidirectional"))
    )
    (net (code "75") (name "unconnected-(IC2-RC2{slash}AN6{slash}P1D{slash}C12IN2-{slash}CVREF{slash}INT2-Pad14)") (class "Default")
      (node (ref "IC2") (pin "14") (pinfunction "RC2/AN6/P1D/C12IN2-/CVREF/INT2_14") (pintype "bidirectional"))
    )
    (net (code "76") (name "unconnected-(IC2-RC3{slash}AN7{slash}P1C{slash}C12IN3-{slash}PGM-Pad7)") (class "Default")
      (node (ref "IC2") (pin "7") (pinfunction "RC3/AN7/P1C/C12IN3-/PGM_7") (pintype "bidirectional"))
    )
    (net (code "77") (name "unconnected-(IC2-RC4{slash}P1B{slash}C12OUT{slash}SRQ-Pad6)") (class "Default")
      (node (ref "IC2") (pin "6") (pinfunction "RC4/P1B/C12OUT/SRQ_6") (pintype "bidirectional"))
    )
    (net (code "78") (name "unconnected-(IC2-RC5{slash}CCP1{slash}P1A{slash}T0CKI-Pad5)") (class "Default")
      (node (ref "IC2") (pin "5") (pinfunction "RC5/CCP1/P1A/T0CKI_5") (pintype "bidirectional"))
    )
    (net (code "79") (name "unconnected-(IC2-RC6{slash}AN8{slash}~{SS{slash}T13CKI{slash}T1OSCI}-Pad8)") (class "Default")
      (node (ref "IC2") (pin "8") (pinfunction "RC6/AN8/~{SS/T13CKI/T1OSCI}_8") (pintype "bidirectional"))
    )
  )
)
